# ComputeModuleNewPsuVersion20191208.net
KiCad netlist of a schematic drawn in EAGLE
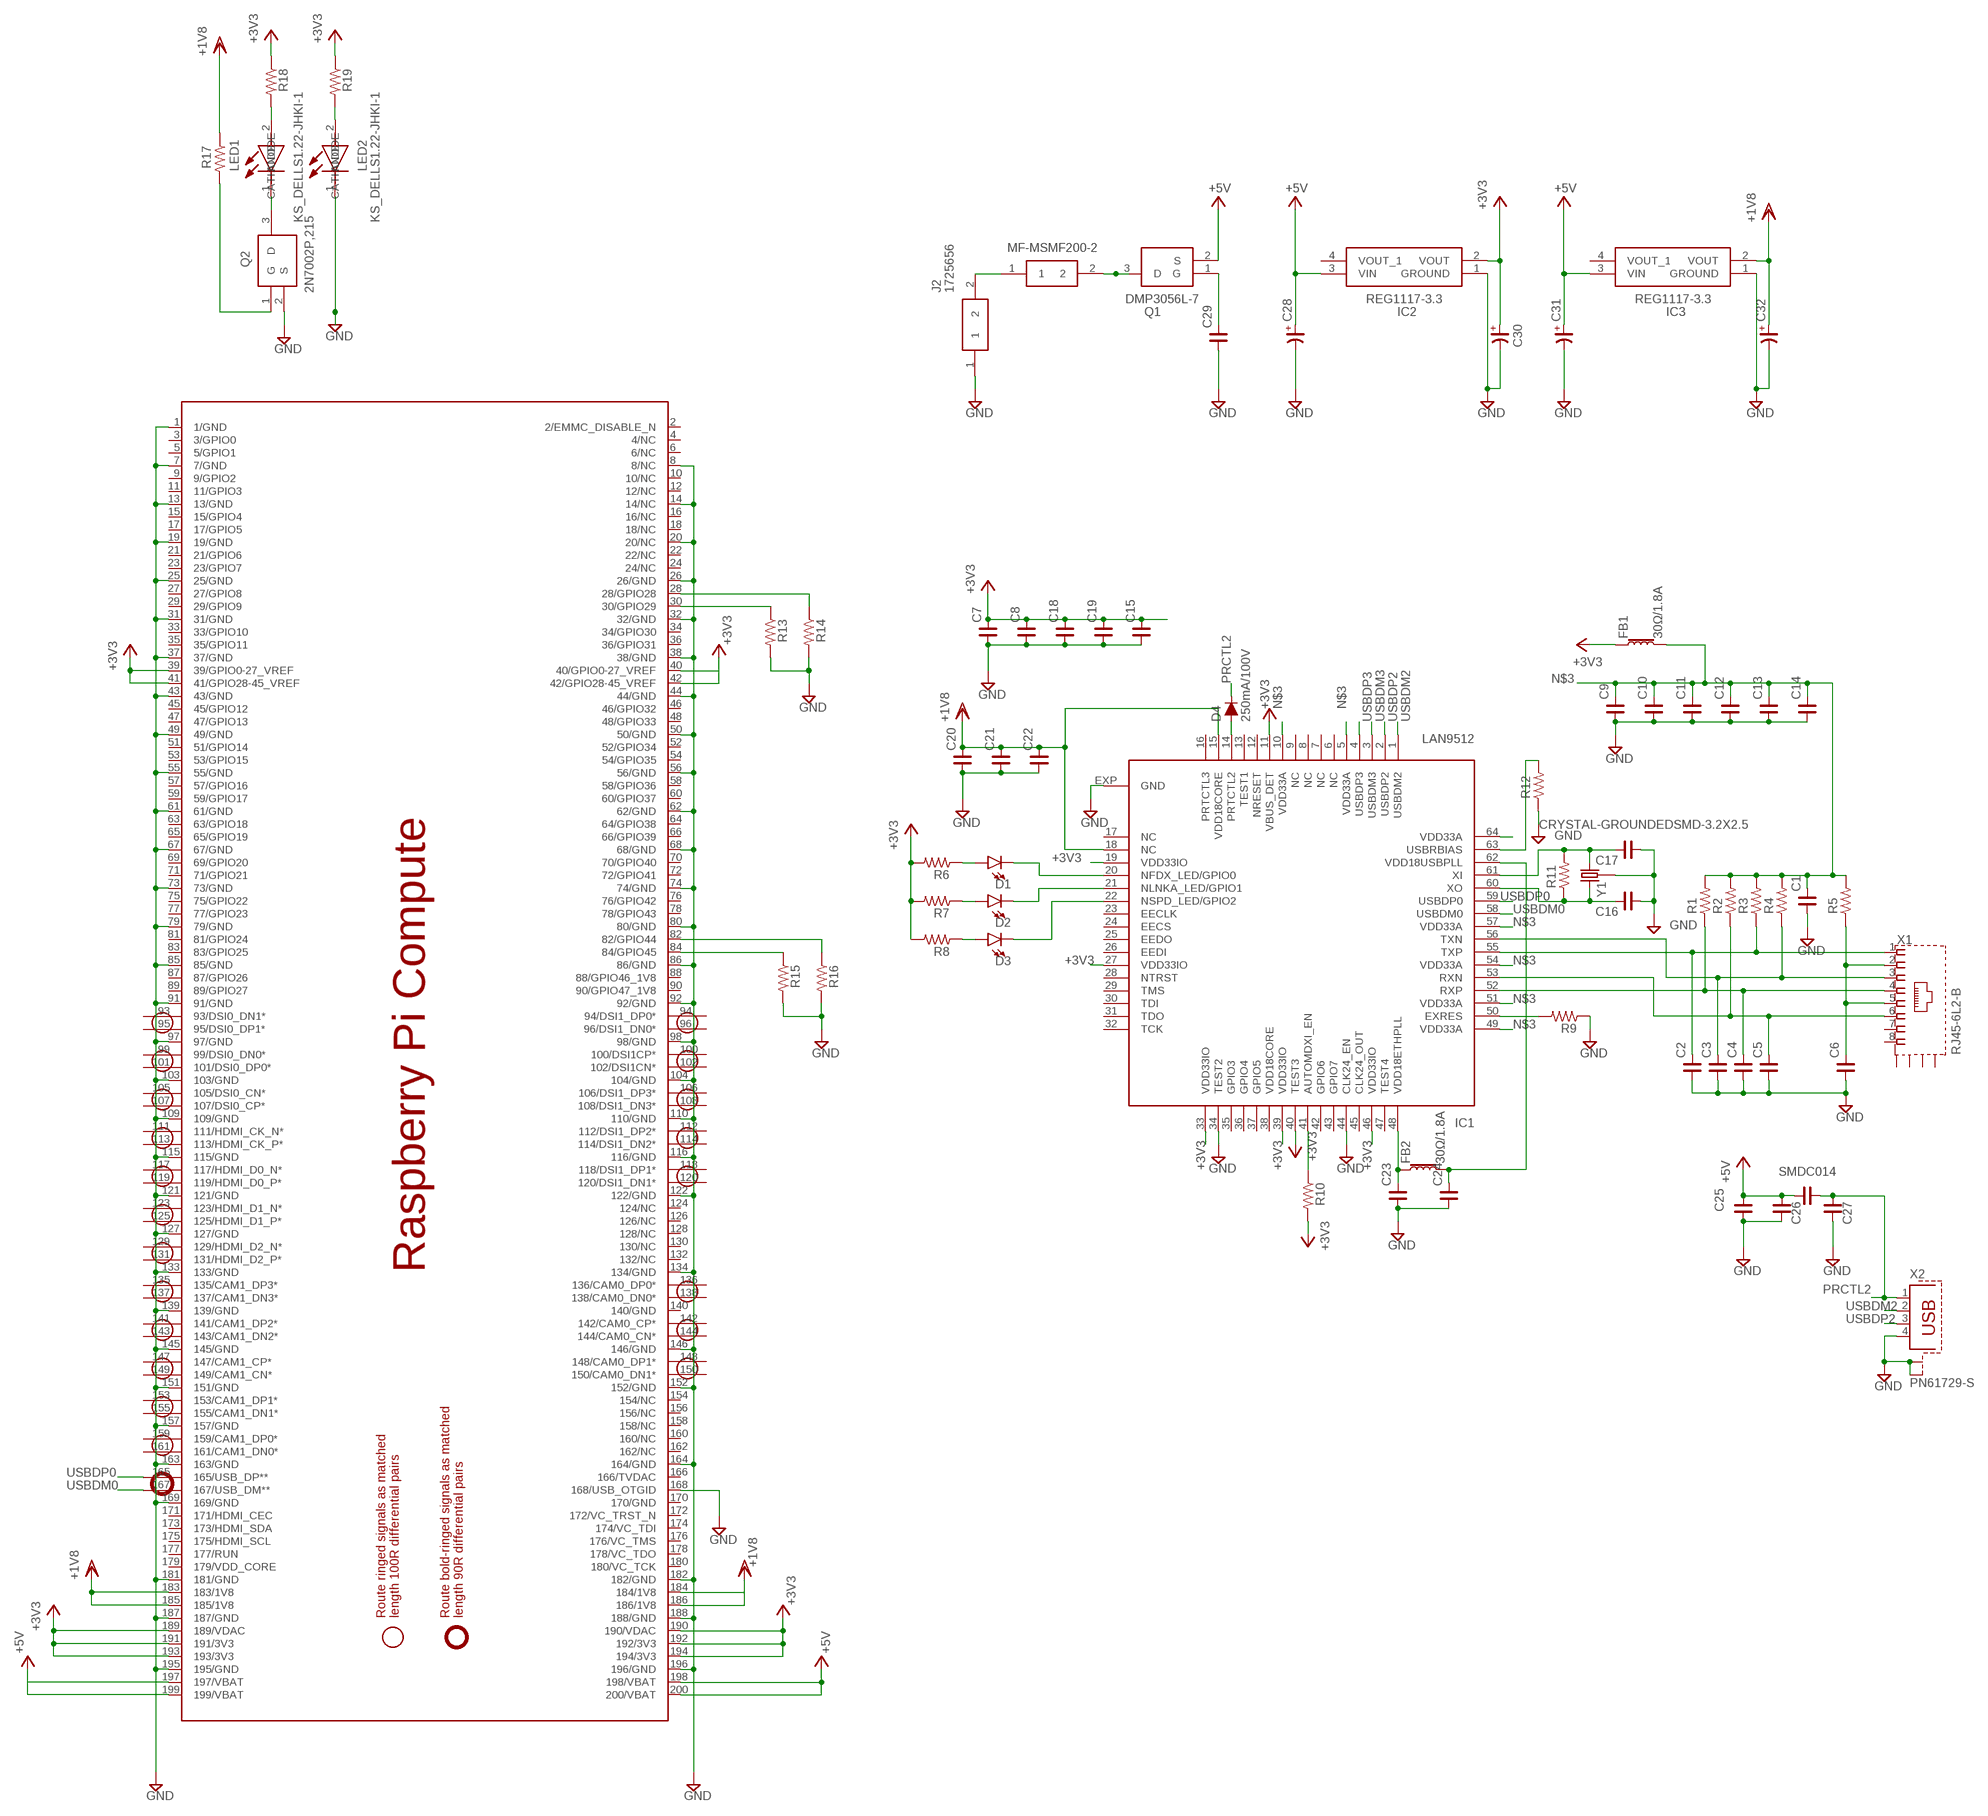
[diagram p0: schematic, sheet 1]

(export (version "E")
  (design (tool "Eeschema 10.0.6"))
  (components
    (comp (ref "C1")
      (value "C_0603")
      (footprint "eagle-import:C0603")
      (libsource (lib "eagle-import") (part "C_0603"))
    )
    (comp (ref "C2")
      (value "C_0603")
      (footprint "eagle-import:C0603")
      (libsource (lib "eagle-import") (part "C_0603"))
    )
    (comp (ref "C3")
      (value "C_0603")
      (footprint "eagle-import:C0603")
      (libsource (lib "eagle-import") (part "C_0603"))
    )
    (comp (ref "C4")
      (value "C_0603")
      (footprint "eagle-import:C0603")
      (libsource (lib "eagle-import") (part "C_0603"))
    )
    (comp (ref "C5")
      (value "C_0603")
      (footprint "eagle-import:C0603")
      (libsource (lib "eagle-import") (part "C_0603"))
    )
    (comp (ref "C6")
      (value "C_0603")
      (footprint "eagle-import:C0603")
      (libsource (lib "eagle-import") (part "C_0603"))
    )
    (comp (ref "C7")
      (value "C_0603")
      (footprint "eagle-import:C0603")
      (libsource (lib "eagle-import") (part "C_0603"))
    )
    (comp (ref "C8")
      (value "C_0603")
      (footprint "eagle-import:C0603")
      (libsource (lib "eagle-import") (part "C_0603"))
    )
    (comp (ref "C9")
      (value "C_0603")
      (footprint "eagle-import:C0603")
      (libsource (lib "eagle-import") (part "C_0603"))
    )
    (comp (ref "C10")
      (value "C_0603")
      (footprint "eagle-import:C0603")
      (libsource (lib "eagle-import") (part "C_0603"))
    )
    (comp (ref "C11")
      (value "C_0603")
      (footprint "eagle-import:C0603")
      (libsource (lib "eagle-import") (part "C_0603"))
    )
    (comp (ref "C12")
      (value "C_0603")
      (footprint "eagle-import:C0603")
      (libsource (lib "eagle-import") (part "C_0603"))
    )
    (comp (ref "C13")
      (value "C_0603")
      (footprint "eagle-import:C0603")
      (libsource (lib "eagle-import") (part "C_0603"))
    )
    (comp (ref "C14")
      (value "C_0603")
      (footprint "eagle-import:C0603")
      (libsource (lib "eagle-import") (part "C_0603"))
    )
    (comp (ref "C15")
      (value "C_0603")
      (footprint "eagle-import:C0603")
      (libsource (lib "eagle-import") (part "C_0603"))
    )
    (comp (ref "C16")
      (value "C_0603")
      (footprint "eagle-import:C0603")
      (libsource (lib "eagle-import") (part "C_0603"))
    )
    (comp (ref "C17")
      (value "C_0603")
      (footprint "eagle-import:C0603")
      (libsource (lib "eagle-import") (part "C_0603"))
    )
    (comp (ref "C18")
      (value "C_0603")
      (footprint "eagle-import:C0603")
      (libsource (lib "eagle-import") (part "C_0603"))
    )
    (comp (ref "C19")
      (value "C_0603")
      (footprint "eagle-import:C0603")
      (libsource (lib "eagle-import") (part "C_0603"))
    )
    (comp (ref "C20")
      (value "C_0603")
      (footprint "eagle-import:C0603")
      (libsource (lib "eagle-import") (part "C_0603"))
    )
    (comp (ref "C21")
      (value "C_0603")
      (footprint "eagle-import:C0603")
      (libsource (lib "eagle-import") (part "C_0603"))
    )
    (comp (ref "C22")
      (value "C_0603")
      (footprint "eagle-import:C0603")
      (libsource (lib "eagle-import") (part "C_0603"))
    )
    (comp (ref "C23")
      (value "C_0603")
      (footprint "eagle-import:C0603")
      (libsource (lib "eagle-import") (part "C_0603"))
    )
    (comp (ref "C24")
      (value "C_0603")
      (footprint "eagle-import:C0603")
      (libsource (lib "eagle-import") (part "C_0603"))
    )
    (comp (ref "C25")
      (value "C_0603")
      (footprint "eagle-import:C0603")
      (libsource (lib "eagle-import") (part "C_0603"))
    )
    (comp (ref "C26")
      (value "C_0603")
      (footprint "eagle-import:C0603")
      (libsource (lib "eagle-import") (part "C_0603"))
    )
    (comp (ref "C27")
      (value "C_0603")
      (footprint "eagle-import:C0603")
      (libsource (lib "eagle-import") (part "C_0603"))
    )
    (comp (ref "C28")
      (value "CP_SV-B")
      (footprint "eagle-import:CSV-B")
      (libsource (lib "eagle-import") (part "CP_SV-B"))
    )
    (comp (ref "C29")
      (value "C_0603")
      (footprint "eagle-import:C0603")
      (libsource (lib "eagle-import") (part "C_0603"))
    )
    (comp (ref "C30")
      (value "CP_SV-B")
      (footprint "eagle-import:CSV-B")
      (libsource (lib "eagle-import") (part "CP_SV-B"))
    )
    (comp (ref "C31")
      (value "CP_SV-B")
      (footprint "eagle-import:CSV-B")
      (libsource (lib "eagle-import") (part "CP_SV-B"))
    )
    (comp (ref "C32")
      (value "CP_SV-B")
      (footprint "eagle-import:CSV-B")
      (libsource (lib "eagle-import") (part "CP_SV-B"))
    )
    (comp (ref "D1")
      (value "LED-FKIT-1206")
      (footprint "eagle-import:FKIT-LED-1206")
      (libsource (lib "eagle-import") (part "LED-FKIT-1206"))
    )
    (comp (ref "D2")
      (value "LED-FKIT-1206")
      (footprint "eagle-import:FKIT-LED-1206")
      (libsource (lib "eagle-import") (part "LED-FKIT-1206"))
    )
    (comp (ref "D3")
      (value "LED-FKIT-1206")
      (footprint "eagle-import:FKIT-LED-1206")
      (libsource (lib "eagle-import") (part "LED-FKIT-1206"))
    )
    (comp (ref "D4")
      (value "250mA/100V")
      (footprint "eagle-import:SOD-323")
      (libsource (lib "eagle-import") (part "DIODE-BAS16J"))
    )
    (comp (ref "F2")
      (value "MF-MSMF200-2")
      (footprint "eagle-import:FUSC4632X85N")
      (fields (field (name "MOUSER_PART_NUMBER") "652-MF-MSMF200-2"))
      (libsource (lib "eagle-import") (part "MF-MSMF200-2"))
    )
    (comp (ref "FB1")
      (value "30Ω/1.8A")
      (footprint "eagle-import:0603")
      (libsource (lib "eagle-import") (part "FERRITE_BEAD-0603"))
    )
    (comp (ref "FB2")
      (value "30Ω/1.8A")
      (footprint "eagle-import:0603")
      (libsource (lib "eagle-import") (part "FERRITE_BEAD-0603"))
    )
    (comp (ref "IC1")
      (value "LAN9512")
      (footprint "eagle-import:QFN64-9X9")
      (libsource (lib "eagle-import") (part "LAN9512"))
    )
    (comp (ref "IC2")
      (value "REG1117-3.3")
      (footprint "eagle-import:SOT230P700X180-4N")
      (fields (field (name "MOUSER_PART_NUMBER") "595-REG1117-3.3"))
      (libsource (lib "eagle-import") (part "REG1117-3.3"))
    )
    (comp (ref "IC3")
      (value "REG1117-3.3")
      (footprint "eagle-import:SOT230P700X180-4N")
      (fields (field (name "MOUSER_PART_NUMBER") "595-REG1117-3.3"))
      (libsource (lib "eagle-import") (part "REG1117-3.3"))
    )
    (comp (ref "J2")
      (value "1725656")
      (footprint "eagle-import:1725656")
      (fields (field (name "MOUSER_PART_NUMBER") "651-1725656"))
      (libsource (lib "eagle-import") (part "1725656"))
    )
    (comp (ref "LED1")
      (value "KS_DELLS1.22-JHKI-1")
      (footprint "eagle-import:KSDELLS122JHKI1")
      (fields
        (field (name "MANUFACTURER_PART_NUMBER") "KS DELLS1.22-JHKI-1")
        (field (name "MOUSER_PART_NUMBER") "720-KSDELLS122A4852")
      )
      (libsource (lib "eagle-import") (part "KS_DELLS1.22-JHKI-1"))
    )
    (comp (ref "LED2")
      (value "KS_DELLS1.22-JHKI-1")
      (footprint "eagle-import:KSDELLS122JHKI1")
      (fields
        (field (name "MANUFACTURER_PART_NUMBER") "KS DELLS1.22-JHKI-1")
        (field (name "MOUSER_PART_NUMBER") "720-KSDELLS122A4852")
      )
      (libsource (lib "eagle-import") (part "KS_DELLS1.22-JHKI-1"))
    )
    (comp (ref "PCB1")
      (value "RPI_COMPUTE")
      (footprint "eagle-import:RPI_COMPUTE")
      (libsource (lib "eagle-import") (part "RPI_COMPUTE"))
    )
    (comp (ref "Q1")
      (value "DMP3056L-7")
      (footprint "eagle-import:SOT96P240X100-3N")
      (fields (field (name "MOUSER_PART_NUMBER") "621-DMP3056L-7"))
      (libsource (lib "eagle-import") (part "DMP3056L-7"))
    )
    (comp (ref "Q2")
      (value "2N7002P,215")
      (footprint "eagle-import:SOT95P230X110-3N")
      (fields (field (name "MOUSER_PART_NUMBER") "771-2N7002P-215"))
      (libsource (lib "eagle-import") (part "2N7002P,215"))
    )
    (comp (ref "R1")
      (value "R_0603")
      (footprint "eagle-import:R0603")
      (libsource (lib "eagle-import") (part "R_0603"))
    )
    (comp (ref "R2")
      (value "R_0603")
      (footprint "eagle-import:R0603")
      (libsource (lib "eagle-import") (part "R_0603"))
    )
    (comp (ref "R3")
      (value "R_0603")
      (footprint "eagle-import:R0603")
      (libsource (lib "eagle-import") (part "R_0603"))
    )
    (comp (ref "R4")
      (value "R_0603")
      (footprint "eagle-import:R0603")
      (libsource (lib "eagle-import") (part "R_0603"))
    )
    (comp (ref "R5")
      (value "R_0603")
      (footprint "eagle-import:R0603")
      (libsource (lib "eagle-import") (part "R_0603"))
    )
    (comp (ref "R6")
      (value "R_0603")
      (footprint "eagle-import:R0603")
      (libsource (lib "eagle-import") (part "R_0603"))
    )
    (comp (ref "R7")
      (value "R_0603")
      (footprint "eagle-import:R0603")
      (libsource (lib "eagle-import") (part "R_0603"))
    )
    (comp (ref "R8")
      (value "R_0603")
      (footprint "eagle-import:R0603")
      (libsource (lib "eagle-import") (part "R_0603"))
    )
    (comp (ref "R9")
      (value "R_0603")
      (footprint "eagle-import:R0603")
      (libsource (lib "eagle-import") (part "R_0603"))
    )
    (comp (ref "R10")
      (value "R_0603")
      (footprint "eagle-import:R0603")
      (libsource (lib "eagle-import") (part "R_0603"))
    )
    (comp (ref "R11")
      (value "R_0603")
      (footprint "eagle-import:R0603")
      (libsource (lib "eagle-import") (part "R_0603"))
    )
    (comp (ref "R12")
      (value "R_0603")
      (footprint "eagle-import:R0603")
      (libsource (lib "eagle-import") (part "R_0603"))
    )
    (comp (ref "R13")
      (value "R_0603")
      (footprint "eagle-import:R0603")
      (libsource (lib "eagle-import") (part "R_0603"))
    )
    (comp (ref "R14")
      (value "R_0603")
      (footprint "eagle-import:R0603")
      (libsource (lib "eagle-import") (part "R_0603"))
    )
    (comp (ref "R15")
      (value "R_0603")
      (footprint "eagle-import:R0603")
      (libsource (lib "eagle-import") (part "R_0603"))
    )
    (comp (ref "R16")
      (value "R_0603")
      (footprint "eagle-import:R0603")
      (libsource (lib "eagle-import") (part "R_0603"))
    )
    (comp (ref "R17")
      (value "R_0603")
      (footprint "eagle-import:R0603")
      (libsource (lib "eagle-import") (part "R_0603"))
    )
    (comp (ref "R18")
      (value "R_0603")
      (footprint "eagle-import:R0603")
      (libsource (lib "eagle-import") (part "R_0603"))
    )
    (comp (ref "R19")
      (value "R_0603")
      (footprint "eagle-import:R0603")
      (libsource (lib "eagle-import") (part "R_0603"))
    )
    (comp (ref "SMDC014")
      (value "C_1812")
      (footprint "eagle-import:C1812")
      (libsource (lib "eagle-import") (part "C_1812"))
    )
    (comp (ref "X1")
      (value "RJ45-6L2-B")
      (footprint "eagle-import:RJ45-SHIELD2")
      (libsource (lib "eagle-import") (part "RJ452-B-6L"))
    )
    (comp (ref "X2")
      (value "PN61729-S")
      (footprint "eagle-import:PN61729-S")
      (libsource (lib "eagle-import") (part "PN61729-S"))
    )
    (comp (ref "Y1")
      (value "CRYSTAL-GROUNDEDSMD-3.2X2.5")
      (footprint "eagle-import:CRYSTAL-SMD-3.2X2.5MM")
      (libsource (lib "eagle-import") (part "CRYSTAL-GROUNDEDSMD-3.2X2.5"))
    )
  )
  (nets
    (net (code "1") (name "+1V8") (class "Default")
      (node (ref "C20") (pin "2") (pinfunction "2_2") (pintype "passive"))
      (node (ref "C21") (pin "2") (pinfunction "2_2") (pintype "passive"))
      (node (ref "C22") (pin "2") (pinfunction "2_2") (pintype "passive"))
      (node (ref "C32") (pin "+") (pinfunction "+_+") (pintype "passive"))
      (node (ref "IC1") (pin "15") (pinfunction "VDD18CORE_15") (pintype "bidirectional"))
      (node (ref "IC1") (pin "18") (pinfunction "NC_18") (pintype "bidirectional"))
      (node (ref "IC3") (pin "2") (pinfunction "VOUT_2") (pintype "output"))
      (node (ref "PCB1") (pin "183") (pinfunction "183/1V8_183") (pintype "bidirectional"))
      (node (ref "PCB1") (pin "185") (pinfunction "185/1V8_185") (pintype "bidirectional"))
      (node (ref "PCB1") (pin "186") (pinfunction "186/1V8_186") (pintype "bidirectional"))
      (node (ref "R17") (pin "1") (pinfunction "1_1") (pintype "passive"))
    )
    (net (code "2") (name "+3V3") (class "Default")
      (node (ref "C15") (pin "2") (pinfunction "2_2") (pintype "passive"))
      (node (ref "C18") (pin "2") (pinfunction "2_2") (pintype "passive"))
      (node (ref "C19") (pin "2") (pinfunction "2_2") (pintype "passive"))
      (node (ref "C30") (pin "+") (pinfunction "+_+") (pintype "passive"))
      (node (ref "C7") (pin "2") (pinfunction "2_2") (pintype "passive"))
      (node (ref "C8") (pin "2") (pinfunction "2_2") (pintype "passive"))
      (node (ref "FB1") (pin "1") (pinfunction "1_1") (pintype "passive"))
      (node (ref "IC1") (pin "11") (pinfunction "VBUS_DET_11") (pintype "bidirectional"))
      (node (ref "IC1") (pin "19") (pinfunction "VDD33IO_19") (pintype "bidirectional"))
      (node (ref "IC1") (pin "27") (pinfunction "VDD33IO_27") (pintype "bidirectional"))
      (node (ref "IC1") (pin "33") (pinfunction "VDD33IO_33") (pintype "bidirectional"))
      (node (ref "IC1") (pin "39") (pinfunction "VDD33IO_39") (pintype "bidirectional"))
      (node (ref "IC1") (pin "40") (pinfunction "TEST3_40") (pintype "bidirectional"))
      (node (ref "IC1") (pin "46") (pinfunction "VDD33IO_46") (pintype "bidirectional"))
      (node (ref "IC2") (pin "2") (pinfunction "VOUT_2") (pintype "output"))
      (node (ref "PCB1") (pin "189") (pinfunction "189/VDAC_189") (pintype "bidirectional"))
      (node (ref "PCB1") (pin "190") (pinfunction "190/VDAC_190") (pintype "bidirectional"))
      (node (ref "PCB1") (pin "191") (pinfunction "191/3V3_191") (pintype "bidirectional"))
      (node (ref "PCB1") (pin "192") (pinfunction "192/3V3_192") (pintype "bidirectional"))
      (node (ref "PCB1") (pin "193") (pinfunction "193/3V3_193") (pintype "bidirectional"))
      (node (ref "PCB1") (pin "194") (pinfunction "194/3V3_194") (pintype "bidirectional"))
      (node (ref "PCB1") (pin "39") (pinfunction "39/GPIO0-27_VREF_39") (pintype "bidirectional"))
      (node (ref "PCB1") (pin "41") (pinfunction "41/GPIO28-45_VREF_41") (pintype "bidirectional"))
      (node (ref "PCB1") (pin "42") (pinfunction "42/GPIO28-45_VREF_42") (pintype "bidirectional"))
      (node (ref "R10") (pin "2") (pinfunction "2_2") (pintype "passive"))
      (node (ref "R18") (pin "1") (pinfunction "1_1") (pintype "passive"))
      (node (ref "R19") (pin "1") (pinfunction "1_1") (pintype "passive"))
      (node (ref "R6") (pin "2") (pinfunction "2_2") (pintype "passive"))
      (node (ref "R7") (pin "2") (pinfunction "2_2") (pintype "passive"))
      (node (ref "R8") (pin "2") (pinfunction "2_2") (pintype "passive"))
    )
    (net (code "3") (name "+5V") (class "Default")
      (node (ref "C25") (pin "2") (pinfunction "2_2") (pintype "passive"))
      (node (ref "C26") (pin "2") (pinfunction "2_2") (pintype "passive"))
      (node (ref "C28") (pin "+") (pinfunction "+_+") (pintype "passive"))
      (node (ref "C31") (pin "+") (pinfunction "+_+") (pintype "passive"))
      (node (ref "IC2") (pin "3") (pinfunction "VIN_3") (pintype "input"))
      (node (ref "IC3") (pin "3") (pinfunction "VIN_3") (pintype "input"))
      (node (ref "PCB1") (pin "198") (pinfunction "198/VBAT_198") (pintype "bidirectional"))
      (node (ref "PCB1") (pin "199") (pinfunction "199/VBAT_199") (pintype "bidirectional"))
      (node (ref "PCB1") (pin "200") (pinfunction "200/VBAT_200") (pintype "bidirectional"))
      (node (ref "Q1") (pin "2") (pinfunction "S_2") (pintype "bidirectional"))
      (node (ref "SMDC014") (pin "1") (pinfunction "1_1") (pintype "passive"))
    )
    (net (code "4") (name "/N$3") (class "Default")
      (node (ref "C1") (pin "2") (pinfunction "2_2") (pintype "passive"))
      (node (ref "C10") (pin "2") (pinfunction "2_2") (pintype "passive"))
      (node (ref "C11") (pin "2") (pinfunction "2_2") (pintype "passive"))
      (node (ref "C12") (pin "2") (pinfunction "2_2") (pintype "passive"))
      (node (ref "C13") (pin "2") (pinfunction "2_2") (pintype "passive"))
      (node (ref "C14") (pin "2") (pinfunction "2_2") (pintype "passive"))
      (node (ref "C9") (pin "2") (pinfunction "2_2") (pintype "passive"))
      (node (ref "FB1") (pin "2") (pinfunction "2_2") (pintype "passive"))
      (node (ref "IC1") (pin "10") (pinfunction "VDD33A_10") (pintype "bidirectional"))
      (node (ref "IC1") (pin "49") (pinfunction "VDD33A_49") (pintype "bidirectional"))
      (node (ref "IC1") (pin "5") (pinfunction "VDD33A_5") (pintype "bidirectional"))
      (node (ref "IC1") (pin "51") (pinfunction "VDD33A_51") (pintype "bidirectional"))
      (node (ref "IC1") (pin "54") (pinfunction "VDD33A_54") (pintype "bidirectional"))
      (node (ref "IC1") (pin "57") (pinfunction "VDD33A_57") (pintype "bidirectional"))
      (node (ref "R1") (pin "2") (pinfunction "2_2") (pintype "passive"))
      (node (ref "R2") (pin "2") (pinfunction "2_2") (pintype "passive"))
      (node (ref "R3") (pin "2") (pinfunction "2_2") (pintype "passive"))
      (node (ref "R4") (pin "2") (pinfunction "2_2") (pintype "passive"))
      (node (ref "R5") (pin "2") (pinfunction "2_2") (pintype "passive"))
    )
    (net (code "5") (name "/PRCTL2") (class "Default")
      (node (ref "C27") (pin "2") (pinfunction "2_2") (pintype "passive"))
      (node (ref "D4") (pin "C") (pinfunction "C_C") (pintype "passive"))
      (node (ref "SMDC014") (pin "2") (pinfunction "2_2") (pintype "passive"))
      (node (ref "X2") (pin "1") (pinfunction "1_1") (pintype "passive"))
    )
    (net (code "6") (name "/USBDM0") (class "Default")
      (node (ref "IC1") (pin "58") (pinfunction "USBDM0_58") (pintype "bidirectional"))
      (node (ref "PCB1") (pin "167") (pinfunction "167/USB_DM**_167") (pintype "bidirectional"))
    )
    (net (code "7") (name "/USBDM2") (class "Default")
      (node (ref "IC1") (pin "1") (pinfunction "USBDM2_1") (pintype "bidirectional"))
      (node (ref "X2") (pin "2") (pinfunction "2_2") (pintype "passive"))
    )
    (net (code "8") (name "/USBDM3") (class "Default")
      (node (ref "IC1") (pin "3") (pinfunction "USBDM3_3") (pintype "bidirectional"))
    )
    (net (code "9") (name "/USBDP0") (class "Default")
      (node (ref "IC1") (pin "59") (pinfunction "USBDP0_59") (pintype "bidirectional"))
      (node (ref "PCB1") (pin "165") (pinfunction "165/USB_DP**_165") (pintype "bidirectional"))
    )
    (net (code "10") (name "/USBDP2") (class "Default")
      (node (ref "IC1") (pin "2") (pinfunction "USBDP2_2") (pintype "bidirectional"))
      (node (ref "X2") (pin "3") (pinfunction "3_3") (pintype "passive"))
    )
    (net (code "11") (name "/USBDP3") (class "Default")
      (node (ref "IC1") (pin "4") (pinfunction "USBDP3_4") (pintype "bidirectional"))
    )
    (net (code "12") (name "GND") (class "Default")
      (node (ref "C1") (pin "1") (pinfunction "1_1") (pintype "passive"))
      (node (ref "C10") (pin "1") (pinfunction "1_1") (pintype "passive"))
      (node (ref "C11") (pin "1") (pinfunction "1_1") (pintype "passive"))
      (node (ref "C12") (pin "1") (pinfunction "1_1") (pintype "passive"))
      (node (ref "C13") (pin "1") (pinfunction "1_1") (pintype "passive"))
      (node (ref "C14") (pin "1") (pinfunction "1_1") (pintype "passive"))
      (node (ref "C15") (pin "1") (pinfunction "1_1") (pintype "passive"))
      (node (ref "C16") (pin "1") (pinfunction "1_1") (pintype "passive"))
      (node (ref "C17") (pin "1") (pinfunction "1_1") (pintype "passive"))
      (node (ref "C18") (pin "1") (pinfunction "1_1") (pintype "passive"))
      (node (ref "C19") (pin "1") (pinfunction "1_1") (pintype "passive"))
      (node (ref "C2") (pin "1") (pinfunction "1_1") (pintype "passive"))
      (node (ref "C20") (pin "1") (pinfunction "1_1") (pintype "passive"))
      (node (ref "C21") (pin "1") (pinfunction "1_1") (pintype "passive"))
      (node (ref "C22") (pin "1") (pinfunction "1_1") (pintype "passive"))
      (node (ref "C23") (pin "1") (pinfunction "1_1") (pintype "passive"))
      (node (ref "C24") (pin "1") (pinfunction "1_1") (pintype "passive"))
      (node (ref "C25") (pin "1") (pinfunction "1_1") (pintype "passive"))
      (node (ref "C26") (pin "1") (pinfunction "1_1") (pintype "passive"))
      (node (ref "C27") (pin "1") (pinfunction "1_1") (pintype "passive"))
      (node (ref "C28") (pin "-") (pinfunction "-_-") (pintype "passive"))
      (node (ref "C29") (pin "1") (pinfunction "1_1") (pintype "passive"))
      (node (ref "C3") (pin "1") (pinfunction "1_1") (pintype "passive"))
      (node (ref "C30") (pin "-") (pinfunction "-_-") (pintype "passive"))
      (node (ref "C31") (pin "-") (pinfunction "-_-") (pintype "passive"))
      (node (ref "C32") (pin "-") (pinfunction "-_-") (pintype "passive"))
      (node (ref "C4") (pin "1") (pinfunction "1_1") (pintype "passive"))
      (node (ref "C5") (pin "1") (pinfunction "1_1") (pintype "passive"))
      (node (ref "C6") (pin "1") (pinfunction "1_1") (pintype "passive"))
      (node (ref "C7") (pin "1") (pinfunction "1_1") (pintype "passive"))
      (node (ref "C8") (pin "1") (pinfunction "1_1") (pintype "passive"))
      (node (ref "C9") (pin "1") (pinfunction "1_1") (pintype "passive"))
      (node (ref "IC1") (pin "34") (pinfunction "TEST2_34") (pintype "bidirectional"))
      (node (ref "IC1") (pin "44") (pinfunction "CLK24_EN_44") (pintype "bidirectional"))
      (node (ref "IC1") (pin "EXP") (pinfunction "GND_EXP") (pintype "bidirectional"))
      (node (ref "IC2") (pin "1") (pinfunction "GROUND_1") (pintype "bidirectional"))
      (node (ref "IC3") (pin "1") (pinfunction "GROUND_1") (pintype "bidirectional"))
      (node (ref "J2") (pin "1") (pinfunction "1_1") (pintype "bidirectional"))
      (node (ref "LED2") (pin "1") (pinfunction "ANODE_1") (pintype "bidirectional"))
      (node (ref "PCB1") (pin "1") (pinfunction "1/GND_1") (pintype "bidirectional"))
      (node (ref "PCB1") (pin "103") (pinfunction "103/GND_103") (pintype "bidirectional"))
      (node (ref "PCB1") (pin "104") (pinfunction "104/GND_104") (pintype "bidirectional"))
      (node (ref "PCB1") (pin "109") (pinfunction "109/GND_109") (pintype "bidirectional"))
      (node (ref "PCB1") (pin "110") (pinfunction "110/GND_110") (pintype "bidirectional"))
      (node (ref "PCB1") (pin "115") (pinfunction "115/GND_115") (pintype "bidirectional"))
      (node (ref "PCB1") (pin "116") (pinfunction "116/GND_116") (pintype "bidirectional"))
      (node (ref "PCB1") (pin "121") (pinfunction "121/GND_121") (pintype "bidirectional"))
      (node (ref "PCB1") (pin "122") (pinfunction "122/GND_122") (pintype "bidirectional"))
      (node (ref "PCB1") (pin "127") (pinfunction "127/GND_127") (pintype "bidirectional"))
      (node (ref "PCB1") (pin "13") (pinfunction "13/GND_13") (pintype "bidirectional"))
      (node (ref "PCB1") (pin "133") (pinfunction "133/GND_133") (pintype "bidirectional"))
      (node (ref "PCB1") (pin "134") (pinfunction "134/GND_134") (pintype "bidirectional"))
      (node (ref "PCB1") (pin "139") (pinfunction "139/GND_139") (pintype "bidirectional"))
      (node (ref "PCB1") (pin "14") (pinfunction "14/NC_14") (pintype "bidirectional"))
      (node (ref "PCB1") (pin "145") (pinfunction "145/GND_145") (pintype "bidirectional"))
      (node (ref "PCB1") (pin "146") (pinfunction "146/GND_146") (pintype "bidirectional"))
      (node (ref "PCB1") (pin "151") (pinfunction "151/GND_151") (pintype "bidirectional"))
      (node (ref "PCB1") (pin "152") (pinfunction "152/GND_152") (pintype "bidirectional"))
      (node (ref "PCB1") (pin "157") (pinfunction "157/GND_157") (pintype "bidirectional"))
      (node (ref "PCB1") (pin "163") (pinfunction "163/GND_163") (pintype "bidirectional"))
      (node (ref "PCB1") (pin "164") (pinfunction "164/GND_164") (pintype "bidirectional"))
      (node (ref "PCB1") (pin "168") (pinfunction "168/USB_OTGID_168") (pintype "bidirectional"))
      (node (ref "PCB1") (pin "169") (pinfunction "169/GND_169") (pintype "bidirectional"))
      (node (ref "PCB1") (pin "181") (pinfunction "181/GND_181") (pintype "bidirectional"))
      (node (ref "PCB1") (pin "182") (pinfunction "182/GND_182") (pintype "bidirectional"))
      (node (ref "PCB1") (pin "187") (pinfunction "187/GND_187") (pintype "bidirectional"))
      (node (ref "PCB1") (pin "188") (pinfunction "188/GND_188") (pintype "bidirectional"))
      (node (ref "PCB1") (pin "19") (pinfunction "19/GND_19") (pintype "bidirectional"))
      (node (ref "PCB1") (pin "195") (pinfunction "195/GND_195") (pintype "bidirectional"))
      (node (ref "PCB1") (pin "196") (pinfunction "196/GND_196") (pintype "bidirectional"))
      (node (ref "PCB1") (pin "20") (pinfunction "20/NC_20") (pintype "bidirectional"))
      (node (ref "PCB1") (pin "25") (pinfunction "25/GND_25") (pintype "bidirectional"))
      (node (ref "PCB1") (pin "26") (pinfunction "26/GND_26") (pintype "bidirectional"))
      (node (ref "PCB1") (pin "31") (pinfunction "31/GND_31") (pintype "bidirectional"))
      (node (ref "PCB1") (pin "32") (pinfunction "32/GND_32") (pintype "bidirectional"))
      (node (ref "PCB1") (pin "37") (pinfunction "37/GND_37") (pintype "bidirectional"))
      (node (ref "PCB1") (pin "38") (pinfunction "38/GND_38") (pintype "bidirectional"))
      (node (ref "PCB1") (pin "43") (pinfunction "43/GND_43") (pintype "bidirectional"))
      (node (ref "PCB1") (pin "44") (pinfunction "44/GND_44") (pintype "bidirectional"))
      (node (ref "PCB1") (pin "49") (pinfunction "49/GND_49") (pintype "bidirectional"))
      (node (ref "PCB1") (pin "50") (pinfunction "50/GND_50") (pintype "bidirectional"))
      (node (ref "PCB1") (pin "55") (pinfunction "55/GND_55") (pintype "bidirectional"))
      (node (ref "PCB1") (pin "56") (pinfunction "56/GND_56") (pintype "bidirectional"))
      (node (ref "PCB1") (pin "61") (pinfunction "61/GND_61") (pintype "bidirectional"))
      (node (ref "PCB1") (pin "62") (pinfunction "62/GND_62") (pintype "bidirectional"))
      (node (ref "PCB1") (pin "67") (pinfunction "67/GND_67") (pintype "bidirectional"))
      (node (ref "PCB1") (pin "68") (pinfunction "68/GND_68") (pintype "bidirectional"))
      (node (ref "PCB1") (pin "7") (pinfunction "7/GND_7") (pintype "bidirectional"))
      (node (ref "PCB1") (pin "73") (pinfunction "73/GND_73") (pintype "bidirectional"))
      (node (ref "PCB1") (pin "74") (pinfunction "74/GND_74") (pintype "bidirectional"))
      (node (ref "PCB1") (pin "79") (pinfunction "79/GND_79") (pintype "bidirectional"))
      (node (ref "PCB1") (pin "8") (pinfunction "8/NC_8") (pintype "bidirectional"))
      (node (ref "PCB1") (pin "80") (pinfunction "80/GND_80") (pintype "bidirectional"))
      (node (ref "PCB1") (pin "85") (pinfunction "85/GND_85") (pintype "bidirectional"))
      (node (ref "PCB1") (pin "86") (pinfunction "86/GND_86") (pintype "bidirectional"))
      (node (ref "PCB1") (pin "91") (pinfunction "91/GND_91") (pintype "bidirectional"))
      (node (ref "PCB1") (pin "92") (pinfunction "92/GND_92") (pintype "bidirectional"))
      (node (ref "PCB1") (pin "97") (pinfunction "97/GND_97") (pintype "bidirectional"))
      (node (ref "PCB1") (pin "98") (pinfunction "98/GND_98") (pintype "bidirectional"))
      (node (ref "Q2") (pin "2") (pinfunction "S_2") (pintype "bidirectional"))
      (node (ref "R12") (pin "1") (pinfunction "1_1") (pintype "passive"))
      (node (ref "R13") (pin "2") (pinfunction "2_2") (pintype "passive"))
      (node (ref "R14") (pin "2") (pinfunction "2_2") (pintype "passive"))
      (node (ref "R15") (pin "2") (pinfunction "2_2") (pintype "passive"))
      (node (ref "R16") (pin "2") (pinfunction "2_2") (pintype "passive"))
      (node (ref "R9") (pin "1") (pinfunction "1_1") (pintype "passive"))
      (node (ref "X2") (pin "4") (pinfunction "4_4") (pintype "passive"))
      (node (ref "X2") (pin "S1") (pinfunction "S1_S1") (pintype "passive"))
      (node (ref "X2") (pin "S2") (pinfunction "S2_S2") (pintype "passive"))
      (node (ref "Y1") (pin "2") (pinfunction "3_2") (pintype "passive"))
      (node (ref "Y1") (pin "4") (pinfunction "3_4") (pintype "passive"))
    )
    (net (code "13") (name "Net-(C6-Pad2)") (class "Default")
      (node (ref "C6") (pin "2") (pinfunction "2_2") (pintype "passive"))
      (node (ref "R5") (pin "1") (pinfunction "1_1") (pintype "passive"))
      (node (ref "X1") (pin "2") (pinfunction "2_2") (pintype "passive"))
      (node (ref "X1") (pin "5") (pinfunction "5_5") (pintype "passive"))
    )
    (net (code "14") (name "Net-(D1-PadA)") (class "Default")
      (node (ref "D1") (pin "A") (pinfunction "A_A") (pintype "passive"))
      (node (ref "R6") (pin "1") (pinfunction "1_1") (pintype "passive"))
    )
    (net (code "15") (name "Net-(D2-PadA)") (class "Default")
      (node (ref "D2") (pin "A") (pinfunction "A_A") (pintype "passive"))
      (node (ref "R7") (pin "1") (pinfunction "1_1") (pintype "passive"))
    )
    (net (code "16") (name "Net-(D3-PadA)") (class "Default")
      (node (ref "D3") (pin "A") (pinfunction "A_A") (pintype "passive"))
      (node (ref "R8") (pin "1") (pinfunction "1_1") (pintype "passive"))
    )
    (net (code "17") (name "Net-(F2-Pad1)") (class "Default")
      (node (ref "F2") (pin "1") (pinfunction "1_1") (pintype "bidirectional"))
      (node (ref "J2") (pin "2") (pinfunction "2_2") (pintype "bidirectional"))
    )
    (net (code "18") (name "Net-(IC1-AUTOMDXI_EN)") (class "Default")
      (node (ref "IC1") (pin "41") (pinfunction "AUTOMDXI_EN_41") (pintype "bidirectional"))
      (node (ref "R10") (pin "1") (pinfunction "1_1") (pintype "passive"))
    )
    (net (code "19") (name "Net-(IC1-EXRES)") (class "Default")
      (node (ref "IC1") (pin "50") (pinfunction "EXRES_50") (pintype "bidirectional"))
      (node (ref "R9") (pin "2") (pinfunction "2_2") (pintype "passive"))
    )
    (net (code "20") (name "Net-(IC1-NFDX_LED{slash}GPIO0)") (class "Default")
      (node (ref "D1") (pin "C") (pinfunction "C_C") (pintype "passive"))
      (node (ref "IC1") (pin "20") (pinfunction "NFDX_LED/GPIO0_20") (pintype "bidirectional"))
    )
    (net (code "21") (name "Net-(IC1-NLNKA_LED{slash}GPIO1)") (class "Default")
      (node (ref "D2") (pin "C") (pinfunction "C_C") (pintype "passive"))
      (node (ref "IC1") (pin "21") (pinfunction "NLNKA_LED/GPIO1_21") (pintype "bidirectional"))
    )
    (net (code "22") (name "Net-(IC1-NSPD_LED{slash}GPIO2)") (class "Default")
      (node (ref "D3") (pin "C") (pinfunction "C_C") (pintype "passive"))
      (node (ref "IC1") (pin "22") (pinfunction "NSPD_LED/GPIO2_22") (pintype "bidirectional"))
    )
    (net (code "23") (name "Net-(IC1-PRTCTL2)") (class "Default")
      (node (ref "D4") (pin "A") (pinfunction "A_A") (pintype "passive"))
      (node (ref "IC1") (pin "14") (pinfunction "PRTCTL2_14") (pintype "bidirectional"))
    )
    (net (code "24") (name "Net-(IC1-RXN)") (class "Default")
      (node (ref "C5") (pin "2") (pinfunction "2_2") (pintype "passive"))
      (node (ref "IC1") (pin "53") (pinfunction "RXN_53") (pintype "bidirectional"))
      (node (ref "R2") (pin "1") (pinfunction "1_1") (pintype "passive"))
      (node (ref "X1") (pin "6") (pinfunction "6_6") (pintype "passive"))
    )
    (net (code "25") (name "Net-(IC1-RXP)") (class "Default")
      (node (ref "C4") (pin "2") (pinfunction "2_2") (pintype "passive"))
      (node (ref "IC1") (pin "52") (pinfunction "RXP_52") (pintype "bidirectional"))
      (node (ref "R1") (pin "1") (pinfunction "1_1") (pintype "passive"))
      (node (ref "X1") (pin "4") (pinfunction "4_4") (pintype "passive"))
    )
    (net (code "26") (name "Net-(IC1-TXN)") (class "Default")
      (node (ref "C3") (pin "2") (pinfunction "2_2") (pintype "passive"))
      (node (ref "IC1") (pin "56") (pinfunction "TXN_56") (pintype "bidirectional"))
      (node (ref "R4") (pin "1") (pinfunction "1_1") (pintype "passive"))
      (node (ref "X1") (pin "3") (pinfunction "3_3") (pintype "passive"))
    )
    (net (code "27") (name "Net-(IC1-TXP)") (class "Default")
      (node (ref "C2") (pin "2") (pinfunction "2_2") (pintype "passive"))
      (node (ref "IC1") (pin "55") (pinfunction "TXP_55") (pintype "bidirectional"))
      (node (ref "R3") (pin "1") (pinfunction "1_1") (pintype "passive"))
      (node (ref "X1") (pin "1") (pinfunction "1_1") (pintype "passive"))
    )
    (net (code "28") (name "Net-(IC1-USBRBIAS)") (class "Default")
      (node (ref "IC1") (pin "63") (pinfunction "USBRBIAS_63") (pintype "bidirectional"))
      (node (ref "R12") (pin "2") (pinfunction "2_2") (pintype "passive"))
    )
    (net (code "29") (name "Net-(IC1-VDD18ETHPLL)") (class "Default")
      (node (ref "C23") (pin "2") (pinfunction "2_2") (pintype "passive"))
      (node (ref "FB2") (pin "1") (pinfunction "1_1") (pintype "passive"))
      (node (ref "IC1") (pin "48") (pinfunction "VDD18ETHPLL_48") (pintype "bidirectional"))
    )
    (net (code "30") (name "Net-(IC1-VDD18USBPLL)") (class "Default")
      (node (ref "C24") (pin "2") (pinfunction "2_2") (pintype "passive"))
      (node (ref "FB2") (pin "2") (pinfunction "2_2") (pintype "passive"))
      (node (ref "IC1") (pin "62") (pinfunction "VDD18USBPLL_62") (pintype "bidirectional"))
    )
    (net (code "31") (name "Net-(IC1-XI)") (class "Default")
      (node (ref "C17") (pin "2") (pinfunction "2_2") (pintype "passive"))
      (node (ref "IC1") (pin "61") (pinfunction "XI_61") (pintype "bidirectional"))
      (node (ref "R11") (pin "2") (pinfunction "2_2") (pintype "passive"))
      (node (ref "Y1") (pin "3") (pinfunction "2_3") (pintype "passive"))
    )
    (net (code "32") (name "Net-(IC1-XO)") (class "Default")
      (node (ref "C16") (pin "2") (pinfunction "2_2") (pintype "passive"))
      (node (ref "IC1") (pin "60") (pinfunction "XO_60") (pintype "bidirectional"))
      (node (ref "R11") (pin "1") (pinfunction "1_1") (pintype "passive"))
      (node (ref "Y1") (pin "1") (pinfunction "1_1") (pintype "passive"))
    )
    (net (code "33") (name "Net-(LED1-ANODE)") (class "Default")
      (node (ref "LED1") (pin "1") (pinfunction "ANODE_1") (pintype "bidirectional"))
      (node (ref "Q2") (pin "3") (pinfunction "D_3") (pintype "bidirectional"))
    )
    (net (code "34") (name "Net-(LED1-CATHODE)") (class "Default")
      (node (ref "LED1") (pin "2") (pinfunction "CATHODE_2") (pintype "bidirectional"))
      (node (ref "R18") (pin "2") (pinfunction "2_2") (pintype "passive"))
    )
    (net (code "35") (name "Net-(LED2-CATHODE)") (class "Default")
      (node (ref "LED2") (pin "2") (pinfunction "CATHODE_2") (pintype "bidirectional"))
      (node (ref "R19") (pin "2") (pinfunction "2_2") (pintype "passive"))
    )
    (net (code "36") (name "Net-(PCB1-28{slash}GPIO28)") (class "Default")
      (node (ref "PCB1") (pin "28") (pinfunction "28/GPIO28_28") (pintype "bidirectional"))
      (node (ref "R14") (pin "1") (pinfunction "1_1") (pintype "passive"))
    )
    (net (code "37") (name "Net-(PCB1-30{slash}GPIO29)") (class "Default")
      (node (ref "PCB1") (pin "30") (pinfunction "30/GPIO29_30") (pintype "bidirectional"))
      (node (ref "R13") (pin "1") (pinfunction "1_1") (pintype "passive"))
    )
    (net (code "38") (name "Net-(PCB1-82{slash}GPIO44)") (class "Default")
      (node (ref "PCB1") (pin "82") (pinfunction "82/GPIO44_82") (pintype "bidirectional"))
      (node (ref "R16") (pin "1") (pinfunction "1_1") (pintype "passive"))
    )
    (net (code "39") (name "Net-(PCB1-84{slash}GPIO45)") (class "Default")
      (node (ref "PCB1") (pin "84") (pinfunction "84/GPIO45_84") (pintype "bidirectional"))
      (node (ref "R15") (pin "1") (pinfunction "1_1") (pintype "passive"))
    )
    (net (code "40") (name "Net-(Q1-D)") (class "Default")
      (node (ref "F2") (pin "2") (pinfunction "2_2") (pintype "bidirectional"))
      (node (ref "Q1") (pin "3") (pinfunction "D_3") (pintype "bidirectional"))
    )
    (net (code "41") (name "Net-(Q1-G)") (class "Default")
      (node (ref "C29") (pin "2") (pinfunction "2_2") (pintype "passive"))
      (node (ref "Q1") (pin "1") (pinfunction "G_1") (pintype "bidirectional"))
    )
    (net (code "42") (name "Net-(Q2-G)") (class "Default")
      (node (ref "Q2") (pin "1") (pinfunction "G_1") (pintype "bidirectional"))
      (node (ref "R17") (pin "2") (pinfunction "2_2") (pintype "passive"))
    )
    (net (code "43") (name "unconnected-(IC1-CLK24_OUT-Pad45)") (class "Default")
      (node (ref "IC1") (pin "45") (pinfunction "CLK24_OUT_45") (pintype "bidirectional"))
    )
    (net (code "44") (name "unconnected-(IC1-EECLK-Pad23)") (class "Default")
      (node (ref "IC1") (pin "23") (pinfunction "EECLK_23") (pintype "bidirectional"))
    )
    (net (code "45") (name "unconnected-(IC1-EECS-Pad24)") (class "Default")
      (node (ref "IC1") (pin "24") (pinfunction "EECS_24") (pintype "bidirectional"))
    )
    (net (code "46") (name "unconnected-(IC1-EEDI-Pad26)") (class "Default")
      (node (ref "IC1") (pin "26") (pinfunction "EEDI_26") (pintype "bidirectional"))
    )
    (net (code "47") (name "unconnected-(IC1-EEDO-Pad25)") (class "Default")
      (node (ref "IC1") (pin "25") (pinfunction "EEDO_25") (pintype "bidirectional"))
    )
    (net (code "48") (name "unconnected-(IC1-GPIO3-Pad35)") (class "Default")
      (node (ref "IC1") (pin "35") (pinfunction "GPIO3_35") (pintype "bidirectional"))
    )
    (net (code "49") (name "unconnected-(IC1-GPIO4-Pad36)") (class "Default")
      (node (ref "IC1") (pin "36") (pinfunction "GPIO4_36") (pintype "bidirectional"))
    )
    (net (code "50") (name "unconnected-(IC1-GPIO5-Pad37)") (class "Default")
      (node (ref "IC1") (pin "37") (pinfunction "GPIO5_37") (pintype "bidirectional"))
    )
    (net (code "51") (name "unconnected-(IC1-GPIO6-Pad42)") (class "Default")
      (node (ref "IC1") (pin "42") (pinfunction "GPIO6_42") (pintype "bidirectional"))
    )
    (net (code "52") (name "unconnected-(IC1-GPIO7-Pad43)") (class "Default")
      (node (ref "IC1") (pin "43") (pinfunction "GPIO7_43") (pintype "bidirectional"))
    )
    (net (code "53") (name "unconnected-(IC1-NC-Pad6)") (class "Default")
      (node (ref "IC1") (pin "6") (pinfunction "NC_6") (pintype "bidirectional"))
    )
    (net (code "54") (name "unconnected-(IC1-NC-Pad7)") (class "Default")
      (node (ref "IC1") (pin "7") (pinfunction "NC_7") (pintype "bidirectional"))
    )
    (net (code "55") (name "unconnected-(IC1-NC-Pad8)") (class "Default")
      (node (ref "IC1") (pin "8") (pinfunction "NC_8") (pintype "bidirectional"))
    )
    (net (code "56") (name "unconnected-(IC1-NC-Pad9)") (class "Default")
      (node (ref "IC1") (pin "9") (pinfunction "NC_9") (pintype "bidirectional"))
    )
    (net (code "57") (name "unconnected-(IC1-NC-Pad17)") (class "Default")
      (node (ref "IC1") (pin "17") (pinfunction "NC_17") (pintype "bidirectional"))
    )
    (net (code "58") (name "unconnected-(IC1-NRESET-Pad12)") (class "Default")
      (node (ref "IC1") (pin "12") (pinfunction "NRESET_12") (pintype "bidirectional"))
    )
    (net (code "59") (name "unconnected-(IC1-NTRST-Pad28)") (class "Default")
      (node (ref "IC1") (pin "28") (pinfunction "NTRST_28") (pintype "bidirectional"))
    )
    (net (code "60") (name "unconnected-(IC1-PRTCTL3-Pad16)") (class "Default")
      (node (ref "IC1") (pin "16") (pinfunction "PRTCTL3_16") (pintype "bidirectional"))
    )
    (net (code "61") (name "unconnected-(IC1-TCK-Pad32)") (class "Default")
      (node (ref "IC1") (pin "32") (pinfunction "TCK_32") (pintype "bidirectional"))
    )
    (net (code "62") (name "unconnected-(IC1-TDI-Pad30)") (class "Default")
      (node (ref "IC1") (pin "30") (pinfunction "TDI_30") (pintype "bidirectional"))
    )
    (net (code "63") (name "unconnected-(IC1-TDO-Pad31)") (class "Default")
      (node (ref "IC1") (pin "31") (pinfunction "TDO_31") (pintype "bidirectional"))
    )
    (net (code "64") (name "unconnected-(IC1-TEST1-Pad13)") (class "Default")
      (node (ref "IC1") (pin "13") (pinfunction "TEST1_13") (pintype "bidirectional"))
    )
    (net (code "65") (name "unconnected-(IC1-TEST4-Pad47)") (class "Default")
      (node (ref "IC1") (pin "47") (pinfunction "TEST4_47") (pintype "bidirectional"))
    )
    (net (code "66") (name "unconnected-(IC1-TMS-Pad29)") (class "Default")
      (node (ref "IC1") (pin "29") (pinfunction "TMS_29") (pintype "bidirectional"))
    )
    (net (code "67") (name "unconnected-(IC1-VDD18CORE-Pad38)") (class "Default")
      (node (ref "IC1") (pin "38") (pinfunction "VDD18CORE_38") (pintype "bidirectional"))
    )
    (net (code "68") (name "unconnected-(IC1-VDD33A-Pad64)") (class "Default")
      (node (ref "IC1") (pin "64") (pinfunction "VDD33A_64") (pintype "bidirectional"))
    )
    (net (code "69") (name "unconnected-(IC2-VOUT_1-Pad4)") (class "Default")
      (node (ref "IC2") (pin "4") (pinfunction "VOUT_1_4") (pintype "output"))
    )
    (net (code "70") (name "unconnected-(IC3-VOUT_1-Pad4)") (class "Default")
      (node (ref "IC3") (pin "4") (pinfunction "VOUT_1_4") (pintype "output"))
    )
    (net (code "71") (name "unconnected-(PCB1-2{slash}EMMC_DISABLE_N-Pad2)") (class "Default")
      (node (ref "PCB1") (pin "2") (pinfunction "2/EMMC_DISABLE_N_2") (pintype "bidirectional"))
    )
    (net (code "72") (name "unconnected-(PCB1-3{slash}GPIO0-Pad3)") (class "Default")
      (node (ref "PCB1") (pin "3") (pinfunction "3/GPIO0_3") (pintype "bidirectional"))
    )
    (net (code "73") (name "unconnected-(PCB1-4{slash}NC-Pad4)") (class "Default")
      (node (ref "PCB1") (pin "4") (pinfunction "4/NC_4") (pintype "bidirectional"))
    )
    (net (code "74") (name "unconnected-(PCB1-5{slash}GPIO1-Pad5)") (class "Default")
      (node (ref "PCB1") (pin "5") (pinfunction "5/GPIO1_5") (pintype "bidirectional"))
    )
    (net (code "75") (name "unconnected-(PCB1-6{slash}NC-Pad6)") (class "Default")
      (node (ref "PCB1") (pin "6") (pinfunction "6/NC_6") (pintype "bidirectional"))
    )
    (net (code "76") (name "unconnected-(PCB1-9{slash}GPIO2-Pad9)") (class "Default")
      (node (ref "PCB1") (pin "9") (pinfunction "9/GPIO2_9") (pintype "bidirectional"))
    )
    (net (code "77") (name "unconnected-(PCB1-10{slash}NC-Pad10)") (class "Default")
      (node (ref "PCB1") (pin "10") (pinfunction "10/NC_10") (pintype "bidirectional"))
    )
    (net (code "78") (name "unconnected-(PCB1-11{slash}GPIO3-Pad11)") (class "Default")
      (node (ref "PCB1") (pin "11") (pinfunction "11/GPIO3_11") (pintype "bidirectional"))
    )
    (net (code "79") (name "unconnected-(PCB1-12{slash}NC-Pad12)") (class "Default")
      (node (ref "PCB1") (pin "12") (pinfunction "12/NC_12") (pintype "bidirectional"))
    )
    (net (code "80") (name "unconnected-(PCB1-15{slash}GPIO4-Pad15)") (class "Default")
      (node (ref "PCB1") (pin "15") (pinfunction "15/GPIO4_15") (pintype "bidirectional"))
    )
    (net (code "81") (name "unconnected-(PCB1-16{slash}NC-Pad16)") (class "Default")
      (node (ref "PCB1") (pin "16") (pinfunction "16/NC_16") (pintype "bidirectional"))
    )
    (net (code "82") (name "unconnected-(PCB1-17{slash}GPIO5-Pad17)") (class "Default")
      (node (ref "PCB1") (pin "17") (pinfunction "17/GPIO5_17") (pintype "bidirectional"))
    )
    (net (code "83") (name "unconnected-(PCB1-18{slash}NC-Pad18)") (class "Default")
      (node (ref "PCB1") (pin "18") (pinfunction "18/NC_18") (pintype "bidirectional"))
    )
    (net (code "84") (name "unconnected-(PCB1-21{slash}GPIO6-Pad21)") (class "Default")
      (node (ref "PCB1") (pin "21") (pinfunction "21/GPIO6_21") (pintype "bidirectional"))
    )
    (net (code "85") (name "unconnected-(PCB1-22{slash}NC-Pad22)") (class "Default")
      (node (ref "PCB1") (pin "22") (pinfunction "22/NC_22") (pintype "bidirectional"))
    )
    (net (code "86") (name "unconnected-(PCB1-23{slash}GPIO7-Pad23)") (class "Default")
      (node (ref "PCB1") (pin "23") (pinfunction "23/GPIO7_23") (pintype "bidirectional"))
    )
    (net (code "87") (name "unconnected-(PCB1-24{slash}NC-Pad24)") (class "Default")
      (node (ref "PCB1") (pin "24") (pinfunction "24/NC_24") (pintype "bidirectional"))
    )
    (net (code "88") (name "unconnected-(PCB1-27{slash}GPIO8-Pad27)") (class "Default")
      (node (ref "PCB1") (pin "27") (pinfunction "27/GPIO8_27") (pintype "bidirectional"))
    )
    (net (code "89") (name "unconnected-(PCB1-29{slash}GPIO9-Pad29)") (class "Default")
      (node (ref "PCB1") (pin "29") (pinfunction "29/GPIO9_29") (pintype "bidirectional"))
    )
    (net (code "90") (name "unconnected-(PCB1-33{slash}GPIO10-Pad33)") (class "Default")
      (node (ref "PCB1") (pin "33") (pinfunction "33/GPIO10_33") (pintype "bidirectional"))
    )
    (net (code "91") (name "unconnected-(PCB1-34{slash}GPIO30-Pad34)") (class "Default")
      (node (ref "PCB1") (pin "34") (pinfunction "34/GPIO30_34") (pintype "bidirectional"))
    )
    (net (code "92") (name "unconnected-(PCB1-35{slash}GPIO11-Pad35)") (class "Default")
      (node (ref "PCB1") (pin "35") (pinfunction "35/GPIO11_35") (pintype "bidirectional"))
    )
    (net (code "93") (name "unconnected-(PCB1-36{slash}GPIO31-Pad36)") (class "Default")
      (node (ref "PCB1") (pin "36") (pinfunction "36/GPIO31_36") (pintype "bidirectional"))
    )
    (net (code "94") (name "unconnected-(PCB1-40{slash}GPIO0-27_VREF-Pad40)") (class "Default")
      (node (ref "PCB1") (pin "40") (pinfunction "40/GPIO0-27_VREF_40") (pintype "bidirectional"))
    )
    (net (code "95") (name "unconnected-(PCB1-45{slash}GPIO12-Pad45)") (class "Default")
      (node (ref "PCB1") (pin "45") (pinfunction "45/GPIO12_45") (pintype "bidirectional"))
    )
    (net (code "96") (name "unconnected-(PCB1-46{slash}GPIO32-Pad46)") (class "Default")
      (node (ref "PCB1") (pin "46") (pinfunction "46/GPIO32_46") (pintype "bidirectional"))
    )
    (net (code "97") (name "unconnected-(PCB1-47{slash}GPIO13-Pad47)") (class "Default")
      (node (ref "PCB1") (pin "47") (pinfunction "47/GPIO13_47") (pintype "bidirectional"))
    )
    (net (code "98") (name "unconnected-(PCB1-48{slash}GPIO33-Pad48)") (class "Default")
      (node (ref "PCB1") (pin "48") (pinfunction "48/GPIO33_48") (pintype "bidirectional"))
    )
    (net (code "99") (name "unconnected-(PCB1-51{slash}GPIO14-Pad51)") (class "Default")
      (node (ref "PCB1") (pin "51") (pinfunction "51/GPIO14_51") (pintype "bidirectional"))
    )
    (net (code "100") (name "unconnected-(PCB1-52{slash}GPIO34-Pad52)") (class "Default")
      (node (ref "PCB1") (pin "52") (pinfunction "52/GPIO34_52") (pintype "bidirectional"))
    )
    (net (code "101") (name "unconnected-(PCB1-53{slash}GPIO15-Pad53)") (class "Default")
      (node (ref "PCB1") (pin "53") (pinfunction "53/GPIO15_53") (pintype "bidirectional"))
    )
    (net (code "102") (name "unconnected-(PCB1-54{slash}GPIO35-Pad54)") (class "Default")
      (node (ref "PCB1") (pin "54") (pinfunction "54/GPIO35_54") (pintype "bidirectional"))
    )
    (net (code "103") (name "unconnected-(PCB1-57{slash}GPIO16-Pad57)") (class "Default")
      (node (ref "PCB1") (pin "57") (pinfunction "57/GPIO16_57") (pintype "bidirectional"))
    )
    (net (code "104") (name "unconnected-(PCB1-58{slash}GPIO36-Pad58)") (class "Default")
      (node (ref "PCB1") (pin "58") (pinfunction "58/GPIO36_58") (pintype "bidirectional"))
    )
    (net (code "105") (name "unconnected-(PCB1-59{slash}GPIO17-Pad59)") (class "Default")
      (node (ref "PCB1") (pin "59") (pinfunction "59/GPIO17_59") (pintype "bidirectional"))
    )
    (net (code "106") (name "unconnected-(PCB1-60{slash}GPIO37-Pad60)") (class "Default")
      (node (ref "PCB1") (pin "60") (pinfunction "60/GPIO37_60") (pintype "bidirectional"))
    )
    (net (code "107") (name "unconnected-(PCB1-63{slash}GPIO18-Pad63)") (class "Default")
      (node (ref "PCB1") (pin "63") (pinfunction "63/GPIO18_63") (pintype "bidirectional"))
    )
    (net (code "108") (name "unconnected-(PCB1-64{slash}GPIO38-Pad64)") (class "Default")
      (node (ref "PCB1") (pin "64") (pinfunction "64/GPIO38_64") (pintype "bidirectional"))
    )
    (net (code "109") (name "unconnected-(PCB1-65{slash}GPIO19-Pad65)") (class "Default")
      (node (ref "PCB1") (pin "65") (pinfunction "65/GPIO19_65") (pintype "bidirectional"))
    )
    (net (code "110") (name "unconnected-(PCB1-66{slash}GPIO39-Pad66)") (class "Default")
      (node (ref "PCB1") (pin "66") (pinfunction "66/GPIO39_66") (pintype "bidirectional"))
    )
    (net (code "111") (name "unconnected-(PCB1-69{slash}GPIO20-Pad69)") (class "Default")
      (node (ref "PCB1") (pin "69") (pinfunction "69/GPIO20_69") (pintype "bidirectional"))
    )
    (net (code "112") (name "unconnected-(PCB1-70{slash}GPIO40-Pad70)") (class "Default")
      (node (ref "PCB1") (pin "70") (pinfunction "70/GPIO40_70") (pintype "bidirectional"))
    )
    (net (code "113") (name "unconnected-(PCB1-71{slash}GPIO21-Pad71)") (class "Default")
      (node (ref "PCB1") (pin "71") (pinfunction "71/GPIO21_71") (pintype "bidirectional"))
    )
    (net (code "114") (name "unconnected-(PCB1-72{slash}GPIO41-Pad72)") (class "Default")
      (node (ref "PCB1") (pin "72") (pinfunction "72/GPIO41_72") (pintype "bidirectional"))
    )
    (net (code "115") (name "unconnected-(PCB1-75{slash}GPIO22-Pad75)") (class "Default")
      (node (ref "PCB1") (pin "75") (pinfunction "75/GPIO22_75") (pintype "bidirectional"))
    )
    (net (code "116") (name "unconnected-(PCB1-76{slash}GPIO42-Pad76)") (class "Default")
      (node (ref "PCB1") (pin "76") (pinfunction "76/GPIO42_76") (pintype "bidirectional"))
    )
    (net (code "117") (name "unconnected-(PCB1-77{slash}GPIO23-Pad77)") (class "Default")
      (node (ref "PCB1") (pin "77") (pinfunction "77/GPIO23_77") (pintype "bidirectional"))
    )
    (net (code "118") (name "unconnected-(PCB1-78{slash}GPIO43-Pad78)") (class "Default")
      (node (ref "PCB1") (pin "78") (pinfunction "78/GPIO43_78") (pintype "bidirectional"))
    )
    (net (code "119") (name "unconnected-(PCB1-81{slash}GPIO24-Pad81)") (class "Default")
      (node (ref "PCB1") (pin "81") (pinfunction "81/GPIO24_81") (pintype "bidirectional"))
    )
    (net (code "120") (name "unconnected-(PCB1-83{slash}GPIO25-Pad83)") (class "Default")
      (node (ref "PCB1") (pin "83") (pinfunction "83/GPIO25_83") (pintype "bidirectional"))
    )
    (net (code "121") (name "unconnected-(PCB1-87{slash}GPIO26-Pad87)") (class "Default")
      (node (ref "PCB1") (pin "87") (pinfunction "87/GPIO26_87") (pintype "bidirectional"))
    )
    (net (code "122") (name "unconnected-(PCB1-88{slash}GPIO46_1V8-Pad88)") (class "Default")
      (node (ref "PCB1") (pin "88") (pinfunction "88/GPIO46_1V8_88") (pintype "bidirectional"))
    )
    (net (code "123") (name "unconnected-(PCB1-89{slash}GPIO27-Pad89)") (class "Default")
      (node (ref "PCB1") (pin "89") (pinfunction "89/GPIO27_89") (pintype "bidirectional"))
    )
    (net (code "124") (name "unconnected-(PCB1-90{slash}GPIO47_1V8-Pad90)") (class "Default")
      (node (ref "PCB1") (pin "90") (pinfunction "90/GPIO47_1V8_90") (pintype "bidirectional"))
    )
    (net (code "125") (name "unconnected-(PCB1-93{slash}DSI0_DN1*-Pad93)") (class "Default")
      (node (ref "PCB1") (pin "93") (pinfunction "93/DSI0_DN1*_93") (pintype "bidirectional"))
    )
    (net (code "126") (name "unconnected-(PCB1-94{slash}DSI1_DP0*-Pad94)") (class "Default")
      (node (ref "PCB1") (pin "94") (pinfunction "94/DSI1_DP0*_94") (pintype "bidirectional"))
    )
    (net (code "127") (name "unconnected-(PCB1-95{slash}DSI0_DP1*-Pad95)") (class "Default")
      (node (ref "PCB1") (pin "95") (pinfunction "95/DSI0_DP1*_95") (pintype "bidirectional"))
    )
    (net (code "128") (name "unconnected-(PCB1-96{slash}DSI1_DN0*-Pad96)") (class "Default")
      (node (ref "PCB1") (pin "96") (pinfunction "96/DSI1_DN0*_96") (pintype "bidirectional"))
    )
    (net (code "129") (name "unconnected-(PCB1-99{slash}DSI0_DN0*-Pad99)") (class "Default")
      (node (ref "PCB1") (pin "99") (pinfunction "99/DSI0_DN0*_99") (pintype "bidirectional"))
    )
    (net (code "130") (name "unconnected-(PCB1-100{slash}DSI1CP*-Pad100)") (class "Default")
      (node (ref "PCB1") (pin "100") (pinfunction "100/DSI1CP*_100") (pintype "bidirectional"))
    )
    (net (code "131") (name "unconnected-(PCB1-101{slash}DSI0_DP0*-Pad101)") (class "Default")
      (node (ref "PCB1") (pin "101") (pinfunction "101/DSI0_DP0*_101") (pintype "bidirectional"))
    )
    (net (code "132") (name "unconnected-(PCB1-102{slash}DSI1CN*-Pad102)") (class "Default")
      (node (ref "PCB1") (pin "102") (pinfunction "102/DSI1CN*_102") (pintype "bidirectional"))
    )
    (net (code "133") (name "unconnected-(PCB1-105{slash}DSI0_CN*-Pad105)") (class "Default")
      (node (ref "PCB1") (pin "105") (pinfunction "105/DSI0_CN*_105") (pintype "bidirectional"))
    )
    (net (code "134") (name "unconnected-(PCB1-106{slash}DSI1_DP3*-Pad106)") (class "Default")
      (node (ref "PCB1") (pin "106") (pinfunction "106/DSI1_DP3*_106") (pintype "bidirectional"))
    )
    (net (code "135") (name "unconnected-(PCB1-107{slash}DSI0_CP*-Pad107)") (class "Default")
      (node (ref "PCB1") (pin "107") (pinfunction "107/DSI0_CP*_107") (pintype "bidirectional"))
    )
    (net (code "136") (name "unconnected-(PCB1-108{slash}DSI1_DN3*-Pad108)") (class "Default")
      (node (ref "PCB1") (pin "108") (pinfunction "108/DSI1_DN3*_108") (pintype "bidirectional"))
    )
    (net (code "137") (name "unconnected-(PCB1-111{slash}HDMI_CK_N*-Pad111)") (class "Default")
      (node (ref "PCB1") (pin "111") (pinfunction "111/HDMI_CK_N*_111") (pintype "bidirectional"))
    )
    (net (code "138") (name "unconnected-(PCB1-112{slash}DSI1_DP2*-Pad112)") (class "Default")
      (node (ref "PCB1") (pin "112") (pinfunction "112/DSI1_DP2*_112") (pintype "bidirectional"))
    )
    (net (code "139") (name "unconnected-(PCB1-113{slash}HDMI_CK_P*-Pad113)") (class "Default")
      (node (ref "PCB1") (pin "113") (pinfunction "113/HDMI_CK_P*_113") (pintype "bidirectional"))
    )
    (net (code "140") (name "unconnected-(PCB1-114{slash}DSI1_DN2*-Pad114)") (class "Default")
      (node (ref "PCB1") (pin "114") (pinfunction "114/DSI1_DN2*_114") (pintype "bidirectional"))
    )
    (net (code "141") (name "unconnected-(PCB1-117{slash}HDMI_D0_N*-Pad117)") (class "Default")
      (node (ref "PCB1") (pin "117") (pinfunction "117/HDMI_D0_N*_117") (pintype "bidirectional"))
    )
    (net (code "142") (name "unconnected-(PCB1-118{slash}DSI1_DP1*-Pad118)") (class "Default")
      (node (ref "PCB1") (pin "118") (pinfunction "118/DSI1_DP1*_118") (pintype "bidirectional"))
    )
    (net (code "143") (name "unconnected-(PCB1-119{slash}HDMI_D0_P*-Pad119)") (class "Default")
      (node (ref "PCB1") (pin "119") (pinfunction "119/HDMI_D0_P*_119") (pintype "bidirectional"))
    )
    (net (code "144") (name "unconnected-(PCB1-120{slash}DSI1_DN1*-Pad120)") (class "Default")
      (node (ref "PCB1") (pin "120") (pinfunction "120/DSI1_DN1*_120") (pintype "bidirectional"))
    )
    (net (code "145") (name "unconnected-(PCB1-123{slash}HDMI_D1_N*-Pad123)") (class "Default")
      (node (ref "PCB1") (pin "123") (pinfunction "123/HDMI_D1_N*_123") (pintype "bidirectional"))
    )
    (net (code "146") (name "unconnected-(PCB1-124{slash}NC-Pad124)") (class "Default")
      (node (ref "PCB1") (pin "124") (pinfunction "124/NC_124") (pintype "bidirectional"))
    )
    (net (code "147") (name "unconnected-(PCB1-125{slash}HDMI_D1_P*-Pad125)") (class "Default")
      (node (ref "PCB1") (pin "125") (pinfunction "125/HDMI_D1_P*_125") (pintype "bidirectional"))
    )
    (net (code "148") (name "unconnected-(PCB1-126{slash}NC-Pad126)") (class "Default")
      (node (ref "PCB1") (pin "126") (pinfunction "126/NC_126") (pintype "bidirectional"))
    )
    (net (code "149") (name "unconnected-(PCB1-128{slash}NC-Pad128)") (class "Default")
      (node (ref "PCB1") (pin "128") (pinfunction "128/NC_128") (pintype "bidirectional"))
    )
    (net (code "150") (name "unconnected-(PCB1-129{slash}HDMI_D2_N*-Pad129)") (class "Default")
      (node (ref "PCB1") (pin "129") (pinfunction "129/HDMI_D2_N*_129") (pintype "bidirectional"))
    )
    (net (code "151") (name "unconnected-(PCB1-130{slash}NC-Pad130)") (class "Default")
      (node (ref "PCB1") (pin "130") (pinfunction "130/NC_130") (pintype "bidirectional"))
    )
    (net (code "152") (name "unconnected-(PCB1-131{slash}HDMI_D2_P*-Pad131)") (class "Default")
      (node (ref "PCB1") (pin "131") (pinfunction "131/HDMI_D2_P*_131") (pintype "bidirectional"))
    )
    (net (code "153") (name "unconnected-(PCB1-132{slash}NC-Pad132)") (class "Default")
      (node (ref "PCB1") (pin "132") (pinfunction "132/NC_132") (pintype "bidirectional"))
    )
    (net (code "154") (name "unconnected-(PCB1-135{slash}CAM1_DP3*-Pad135)") (class "Default")
      (node (ref "PCB1") (pin "135") (pinfunction "135/CAM1_DP3*_135") (pintype "bidirectional"))
    )
    (net (code "155") (name "unconnected-(PCB1-136{slash}CAM0_DP0*-Pad136)") (class "Default")
      (node (ref "PCB1") (pin "136") (pinfunction "136/CAM0_DP0*_136") (pintype "bidirectional"))
    )
    (net (code "156") (name "unconnected-(PCB1-137{slash}CAM1_DN3*-Pad137)") (class "Default")
      (node (ref "PCB1") (pin "137") (pinfunction "137/CAM1_DN3*_137") (pintype "bidirectional"))
    )
    (net (code "157") (name "unconnected-(PCB1-138{slash}CAM0_DN0*-Pad138)") (class "Default")
      (node (ref "PCB1") (pin "138") (pinfunction "138/CAM0_DN0*_138") (pintype "bidirectional"))
    )
    (net (code "158") (name "unconnected-(PCB1-140{slash}GND-Pad140)") (class "Default")
      (node (ref "PCB1") (pin "140") (pinfunction "140/GND_140") (pintype "bidirectional"))
    )
    (net (code "159") (name "unconnected-(PCB1-141{slash}CAM1_DP2*-Pad141)") (class "Default")
      (node (ref "PCB1") (pin "141") (pinfunction "141/CAM1_DP2*_141") (pintype "bidirectional"))
    )
    (net (code "160") (name "unconnected-(PCB1-142{slash}CAM0_CP*-Pad142)") (class "Default")
      (node (ref "PCB1") (pin "142") (pinfunction "142/CAM0_CP*_142") (pintype "bidirectional"))
    )
    (net (code "161") (name "unconnected-(PCB1-143{slash}CAM1_DN2*-Pad143)") (class "Default")
      (node (ref "PCB1") (pin "143") (pinfunction "143/CAM1_DN2*_143") (pintype "bidirectional"))
    )
    (net (code "162") (name "unconnected-(PCB1-144{slash}CAM0_CN*-Pad144)") (class "Default")
      (node (ref "PCB1") (pin "144") (pinfunction "144/CAM0_CN*_144") (pintype "bidirectional"))
    )
    (net (code "163") (name "unconnected-(PCB1-147{slash}CAM1_CP*-Pad147)") (class "Default")
      (node (ref "PCB1") (pin "147") (pinfunction "147/CAM1_CP*_147") (pintype "bidirectional"))
    )
    (net (code "164") (name "unconnected-(PCB1-148{slash}CAM0_DP1*-Pad148)") (class "Default")
      (node (ref "PCB1") (pin "148") (pinfunction "148/CAM0_DP1*_148") (pintype "bidirectional"))
    )
    (net (code "165") (name "unconnected-(PCB1-149{slash}CAM1_CN*-Pad149)") (class "Default")
      (node (ref "PCB1") (pin "149") (pinfunction "149/CAM1_CN*_149") (pintype "bidirectional"))
    )
    (net (code "166") (name "unconnected-(PCB1-150{slash}CAM0_DN1*-Pad150)") (class "Default")
      (node (ref "PCB1") (pin "150") (pinfunction "150/CAM0_DN1*_150") (pintype "bidirectional"))
    )
    (net (code "167") (name "unconnected-(PCB1-153{slash}CAM1_DP1*-Pad153)") (class "Default")
      (node (ref "PCB1") (pin "153") (pinfunction "153/CAM1_DP1*_153") (pintype "bidirectional"))
    )
    (net (code "168") (name "unconnected-(PCB1-154{slash}NC-Pad154)") (class "Default")
      (node (ref "PCB1") (pin "154") (pinfunction "154/NC_154") (pintype "bidirectional"))
    )
    (net (code "169") (name "unconnected-(PCB1-155{slash}CAM1_DN1*-Pad155)") (class "Default")
      (node (ref "PCB1") (pin "155") (pinfunction "155/CAM1_DN1*_155") (pintype "bidirectional"))
    )
    (net (code "170") (name "unconnected-(PCB1-156{slash}NC-Pad156)") (class "Default")
      (node (ref "PCB1") (pin "156") (pinfunction "156/NC_156") (pintype "bidirectional"))
    )
    (net (code "171") (name "unconnected-(PCB1-158{slash}NC-Pad158)") (class "Default")
      (node (ref "PCB1") (pin "158") (pinfunction "158/NC_158") (pintype "bidirectional"))
    )
    (net (code "172") (name "unconnected-(PCB1-159{slash}CAM1_DP0*-Pad159)") (class "Default")
      (node (ref "PCB1") (pin "159") (pinfunction "159/CAM1_DP0*_159") (pintype "bidirectional"))
    )
    (net (code "173") (name "unconnected-(PCB1-160{slash}NC-Pad160)") (class "Default")
      (node (ref "PCB1") (pin "160") (pinfunction "160/NC_160") (pintype "bidirectional"))
    )
    (net (code "174") (name "unconnected-(PCB1-161{slash}CAM1_DN0*-Pad161)") (class "Default")
      (node (ref "PCB1") (pin "161") (pinfunction "161/CAM1_DN0*_161") (pintype "bidirectional"))
    )
    (net (code "175") (name "unconnected-(PCB1-162{slash}NC-Pad162)") (class "Default")
      (node (ref "PCB1") (pin "162") (pinfunction "162/NC_162") (pintype "bidirectional"))
    )
    (net (code "176") (name "unconnected-(PCB1-166{slash}TVDAC-Pad166)") (class "Default")
      (node (ref "PCB1") (pin "166") (pinfunction "166/TVDAC_166") (pintype "bidirectional"))
    )
    (net (code "177") (name "unconnected-(PCB1-170{slash}GND-Pad170)") (class "Default")
      (node (ref "PCB1") (pin "170") (pinfunction "170/GND_170") (pintype "bidirectional"))
    )
    (net (code "178") (name "unconnected-(PCB1-171{slash}HDMI_CEC-Pad171)") (class "Default")
      (node (ref "PCB1") (pin "171") (pinfunction "171/HDMI_CEC_171") (pintype "bidirectional"))
    )
    (net (code "179") (name "unconnected-(PCB1-172{slash}VC_TRST_N-Pad172)") (class "Default")
      (node (ref "PCB1") (pin "172") (pinfunction "172/VC_TRST_N_172") (pintype "bidirectional"))
    )
    (net (code "180") (name "unconnected-(PCB1-173{slash}HDMI_SDA-Pad173)") (class "Default")
      (node (ref "PCB1") (pin "173") (pinfunction "173/HDMI_SDA_173") (pintype "bidirectional"))
    )
    (net (code "181") (name "unconnected-(PCB1-174{slash}VC_TDI-Pad174)") (class "Default")
      (node (ref "PCB1") (pin "174") (pinfunction "174/VC_TDI_174") (pintype "bidirectional"))
    )
    (net (code "182") (name "unconnected-(PCB1-175{slash}HDMI_SCL-Pad175)") (class "Default")
      (node (ref "PCB1") (pin "175") (pinfunction "175/HDMI_SCL_175") (pintype "bidirectional"))
    )
    (net (code "183") (name "unconnected-(PCB1-176{slash}VC_TMS-Pad176)") (class "Default")
      (node (ref "PCB1") (pin "176") (pinfunction "176/VC_TMS_176") (pintype "bidirectional"))
    )
    (net (code "184") (name "unconnected-(PCB1-177{slash}RUN-Pad177)") (class "Default")
      (node (ref "PCB1") (pin "177") (pinfunction "177/RUN_177") (pintype "bidirectional"))
    )
    (net (code "185") (name "unconnected-(PCB1-178{slash}VC_TDO-Pad178)") (class "Default")
      (node (ref "PCB1") (pin "178") (pinfunction "178/VC_TDO_178") (pintype "bidirectional"))
    )
    (net (code "186") (name "unconnected-(PCB1-179{slash}VDD_CORE-Pad179)") (class "Default")
      (node (ref "PCB1") (pin "179") (pinfunction "179/VDD_CORE_179") (pintype "bidirectional"))
    )
    (net (code "187") (name "unconnected-(PCB1-180{slash}VC_TCK-Pad180)") (class "Default")
      (node (ref "PCB1") (pin "180") (pinfunction "180/VC_TCK_180") (pintype "bidirectional"))
    )
    (net (code "188") (name "unconnected-(PCB1-184{slash}1V8-Pad184)") (class "Default")
      (node (ref "PCB1") (pin "184") (pinfunction "184/1V8_184") (pintype "bidirectional"))
    )
    (net (code "189") (name "unconnected-(PCB1-197{slash}VBAT-Pad197)") (class "Default")
      (node (ref "PCB1") (pin "197") (pinfunction "197/VBAT_197") (pintype "bidirectional"))
    )
    (net (code "190") (name "unconnected-(X1-Pad7)") (class "Default")
      (node (ref "X1") (pin "7") (pinfunction "7_7") (pintype "passive"))
    )
    (net (code "191") (name "unconnected-(X1-Pad8)") (class "Default")
      (node (ref "X1") (pin "8") (pinfunction "8_8") (pintype "passive"))
    )
    (net (code "192") (name "unconnected-(X1-S-PadS1)") (class "Default")
      (node (ref "X1") (pin "S1") (pinfunction "S_S1") (pintype "passive"))
    )
    (net (code "193") (name "unconnected-(X1-S-PadS2)") (class "Default")
      (node (ref "X1") (pin "S2") (pinfunction "S_S2") (pintype "passive"))
    )
    (net (code "194") (name "unconnected-(X1-S-PadS3)") (class "Default")
      (node (ref "X1") (pin "S3") (pinfunction "S_S3") (pintype "passive"))
    )
    (net (code "195") (name "unconnected-(X1-S-PadS4)") (class "Default")
      (node (ref "X1") (pin "S4") (pinfunction "S_S4") (pintype "passive"))
    )
  )
)
